# TK1000_Spolerigg.net
KiCad netlist of a schematic drawn in Altium Designer
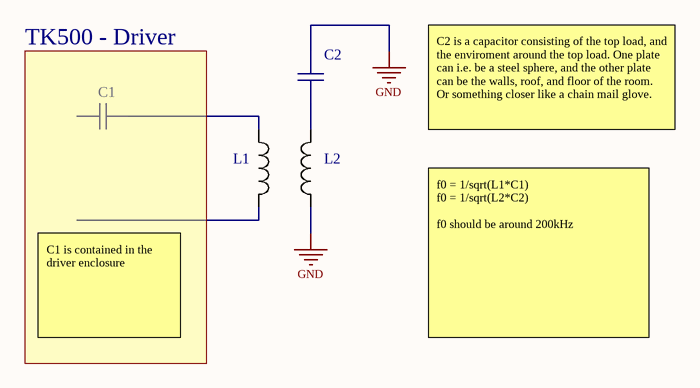
[diagram p0: TK1000_Spolerigg.SchDoc]

(export (version "E")
  (design (tool "Eeschema 10.0.6"))
  (components
    (comp (ref "C1")
      (value "100nF")
      (footprint "CAPC0805(2012)100_N")
      (description "X7R 50V")
      (libsource (lib "OVLib") (part "CAP"))
    )
    (comp (ref "C2")
      (value "100nF")
      (footprint "CAPC0805(2012)100_N")
      (description "X7R 50V")
      (libsource (lib "OVLib") (part "CAP"))
    )
    (comp (ref "L1")
      (value "SMD spoler")
      (footprint "INDP3225X20N")
      (description "SMD inductors og tomme SMD bokser")
      (libsource (lib "OVLib") (part "IND_GENERIC"))
    )
    (comp (ref "L2")
      (value "SMD spoler")
      (footprint "INDP3225X20N")
      (description "SMD inductors og tomme SMD bokser")
      (libsource (lib "OVLib") (part "IND_GENERIC"))
    )
  )
  (nets
    (net (code "1") (name "GND") (class "Default")
      (node (ref "C2") (pin "2") (pinfunction "2_2") (pintype "passive"))
      (node (ref "L2") (pin "2") (pinfunction "2_2") (pintype "passive"))
    )
    (net (code "2") (name "Net-(C1-Pad2)") (class "Default")
      (node (ref "C1") (pin "2") (pinfunction "2_2") (pintype "passive"))
      (node (ref "L1") (pin "1") (pinfunction "1_1") (pintype "passive"))
    )
    (net (code "3") (name "Net-(C2-Pad1)") (class "Default")
      (node (ref "C2") (pin "1") (pinfunction "1_1") (pintype "passive"))
      (node (ref "L2") (pin "1") (pinfunction "1_1") (pintype "passive"))
    )
    (net (code "4") (name "unconnected-(C1-Pad1)") (class "Default")
      (node (ref "C1") (pin "1") (pinfunction "1_1") (pintype "passive"))
    )
    (net (code "5") (name "unconnected-(L1-Pad2)") (class "Default")
      (node (ref "L1") (pin "2") (pinfunction "2_2") (pintype "passive"))
    )
  )
)
